# Atrix_breakout.net
KiCad netlist of a schematic drawn in EAGLE
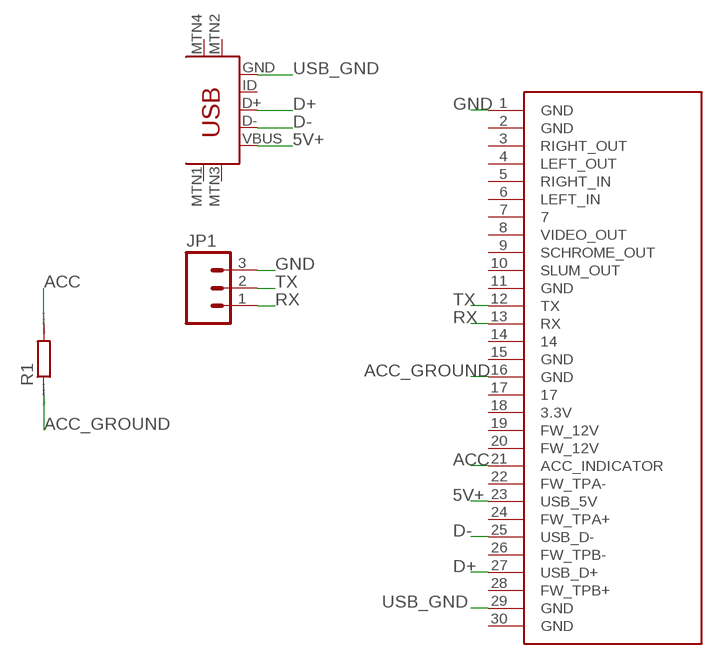
[diagram p0: schematic, sheet 1]

(export (version "E")
  (design (tool "Eeschema 10.0.6"))
  (components
    (comp (ref "JP1")
      (value "M03")
      (footprint "eagle-import:03P")
      (libsource (lib "eagle-import") (part "M03"))
    )
    (comp (ref "R1")
      (value "R0207/10")
      (footprint "eagle-import:0207_10")
      (libsource (lib "eagle-import") (part "R0207/10"))
    )
    (comp (ref "U$1")
      (value "IPOD_CONNECTOR_MALE")
      (footprint "eagle-import:IPOD_MALE_CONNECTOR")
      (libsource (lib "eagle-import") (part "IPOD_CONNECTOR_MALE"))
    )
    (comp (ref "U$3")
      (value "USB-MINIB-5PIN")
      (footprint "eagle-import:USB-MINIB")
      (libsource (lib "eagle-import") (part "USB-MINIB-5PIN"))
    )
  )
  (nets
    (net (code "1") (name "/5V+") (class "Default")
      (node (ref "U$1") (pin "23") (pinfunction "USB_5V_23") (pintype "bidirectional"))
      (node (ref "U$3") (pin "VBUS") (pinfunction "VBUS_VBUS") (pintype "bidirectional"))
    )
    (net (code "2") (name "/ACC") (class "Default")
      (node (ref "R1") (pin "2") (pinfunction "2_2") (pintype "passive"))
      (node (ref "U$1") (pin "21") (pinfunction "ACC_INDICATOR_21") (pintype "bidirectional"))
    )
    (net (code "3") (name "/ACC_GROUND") (class "Default")
      (node (ref "R1") (pin "1") (pinfunction "1_1") (pintype "passive"))
      (node (ref "U$1") (pin "16") (pinfunction "GND_16") (pintype "bidirectional"))
    )
    (net (code "4") (name "/D+") (class "Default")
      (node (ref "U$1") (pin "27") (pinfunction "USB_D+_27") (pintype "bidirectional"))
      (node (ref "U$3") (pin "D+") (pinfunction "D+_D+") (pintype "bidirectional"))
    )
    (net (code "5") (name "/D-") (class "Default")
      (node (ref "U$1") (pin "25") (pinfunction "USB_D-_25") (pintype "bidirectional"))
      (node (ref "U$3") (pin "D-") (pinfunction "D-_D-") (pintype "bidirectional"))
    )
    (net (code "6") (name "/GND") (class "Default")
      (node (ref "JP1") (pin "3") (pinfunction "3_3") (pintype "passive"))
      (node (ref "U$1") (pin "1") (pinfunction "GND_1") (pintype "bidirectional"))
    )
    (net (code "7") (name "/RX") (class "Default")
      (node (ref "JP1") (pin "1") (pinfunction "1_1") (pintype "passive"))
      (node (ref "U$1") (pin "13") (pinfunction "RX_13") (pintype "bidirectional"))
    )
    (net (code "8") (name "/TX") (class "Default")
      (node (ref "JP1") (pin "2") (pinfunction "2_2") (pintype "passive"))
      (node (ref "U$1") (pin "12") (pinfunction "TX_12") (pintype "bidirectional"))
    )
    (net (code "9") (name "/USB_GND") (class "Default")
      (node (ref "U$1") (pin "29") (pinfunction "GND_29") (pintype "bidirectional"))
      (node (ref "U$3") (pin "GND") (pinfunction "GND_GND") (pintype "bidirectional"))
    )
    (net (code "10") (name "unconnected-(U$1-3.3V-Pad18)") (class "Default")
      (node (ref "U$1") (pin "18") (pinfunction "3.3V_18") (pintype "bidirectional"))
    )
    (net (code "11") (name "unconnected-(U$1-FW_12V-Pad19)") (class "Default")
      (node (ref "U$1") (pin "19") (pinfunction "FW_12V_19") (pintype "bidirectional"))
    )
    (net (code "12") (name "unconnected-(U$1-FW_12V-Pad20)") (class "Default")
      (node (ref "U$1") (pin "20") (pinfunction "FW_12V_20") (pintype "bidirectional"))
    )
    (net (code "13") (name "unconnected-(U$1-FW_TPA+-Pad24)") (class "Default")
      (node (ref "U$1") (pin "24") (pinfunction "FW_TPA+_24") (pintype "bidirectional"))
    )
    (net (code "14") (name "unconnected-(U$1-FW_TPA--Pad22)") (class "Default")
      (node (ref "U$1") (pin "22") (pinfunction "FW_TPA-_22") (pintype "bidirectional"))
    )
    (net (code "15") (name "unconnected-(U$1-FW_TPB+-Pad28)") (class "Default")
      (node (ref "U$1") (pin "28") (pinfunction "FW_TPB+_28") (pintype "bidirectional"))
    )
    (net (code "16") (name "unconnected-(U$1-FW_TPB--Pad26)") (class "Default")
      (node (ref "U$1") (pin "26") (pinfunction "FW_TPB-_26") (pintype "bidirectional"))
    )
    (net (code "17") (name "unconnected-(U$1-GND-Pad2)") (class "Default")
      (node (ref "U$1") (pin "2") (pinfunction "GND_2") (pintype "bidirectional"))
    )
    (net (code "18") (name "unconnected-(U$1-GND-Pad11)") (class "Default")
      (node (ref "U$1") (pin "11") (pinfunction "GND_11") (pintype "bidirectional"))
    )
    (net (code "19") (name "unconnected-(U$1-GND-Pad15)") (class "Default")
      (node (ref "U$1") (pin "15") (pinfunction "GND_15") (pintype "bidirectional"))
    )
    (net (code "20") (name "unconnected-(U$1-GND-Pad30)") (class "Default")
      (node (ref "U$1") (pin "30") (pinfunction "GND_30") (pintype "bidirectional"))
    )
    (net (code "21") (name "unconnected-(U$1-LEFT_IN-Pad6)") (class "Default")
      (node (ref "U$1") (pin "6") (pinfunction "LEFT_IN_6") (pintype "bidirectional"))
    )
    (net (code "22") (name "unconnected-(U$1-LEFT_OUT-Pad4)") (class "Default")
      (node (ref "U$1") (pin "4") (pinfunction "LEFT_OUT_4") (pintype "bidirectional"))
    )
    (net (code "23") (name "unconnected-(U$1-Pad7)") (class "Default")
      (node (ref "U$1") (pin "7") (pinfunction "7_7") (pintype "bidirectional"))
    )
    (net (code "24") (name "unconnected-(U$1-Pad14)") (class "Default")
      (node (ref "U$1") (pin "14") (pinfunction "14_14") (pintype "bidirectional"))
    )
    (net (code "25") (name "unconnected-(U$1-Pad17)") (class "Default")
      (node (ref "U$1") (pin "17") (pinfunction "17_17") (pintype "bidirectional"))
    )
    (net (code "26") (name "unconnected-(U$1-RIGHT_IN-Pad5)") (class "Default")
      (node (ref "U$1") (pin "5") (pinfunction "RIGHT_IN_5") (pintype "bidirectional"))
    )
    (net (code "27") (name "unconnected-(U$1-RIGHT_OUT-Pad3)") (class "Default")
      (node (ref "U$1") (pin "3") (pinfunction "RIGHT_OUT_3") (pintype "bidirectional"))
    )
    (net (code "28") (name "unconnected-(U$1-SCHROME_OUT-Pad9)") (class "Default")
      (node (ref "U$1") (pin "9") (pinfunction "SCHROME_OUT_9") (pintype "bidirectional"))
    )
    (net (code "29") (name "unconnected-(U$1-SLUM_OUT-Pad10)") (class "Default")
      (node (ref "U$1") (pin "10") (pinfunction "SLUM_OUT_10") (pintype "bidirectional"))
    )
    (net (code "30") (name "unconnected-(U$1-VIDEO_OUT-Pad8)") (class "Default")
      (node (ref "U$1") (pin "8") (pinfunction "VIDEO_OUT_8") (pintype "bidirectional"))
    )
    (net (code "31") (name "unconnected-(U$3-MTN1-PadMTN3)") (class "Default")
      (node (ref "U$3") (pin "MTN3") (pinfunction "MTN1_MTN3") (pintype "bidirectional"))
    )
    (net (code "32") (name "unconnected-(U$3-MTN2-PadMTN1)") (class "Default")
      (node (ref "U$3") (pin "MTN1") (pinfunction "MTN2_MTN1") (pintype "bidirectional"))
    )
    (net (code "33") (name "unconnected-(U$3-MTN3-PadMTN2)") (class "Default")
      (node (ref "U$3") (pin "MTN2") (pinfunction "MTN3_MTN2") (pintype "bidirectional"))
    )
    (net (code "34") (name "unconnected-(U$3-PadID)") (class "Default")
      (node (ref "U$3") (pin "ID") (pinfunction "ID_ID") (pintype "bidirectional"))
    )
    (net (code "35") (name "unconnected-(U$3-PadMTN4)") (class "Default")
      (node (ref "U$3") (pin "MTN4") (pinfunction "MTN4_MTN4") (pintype "bidirectional"))
    )
  )
)
